# pi-io-board.net
KiCad netlist of a schematic drawn in EAGLE
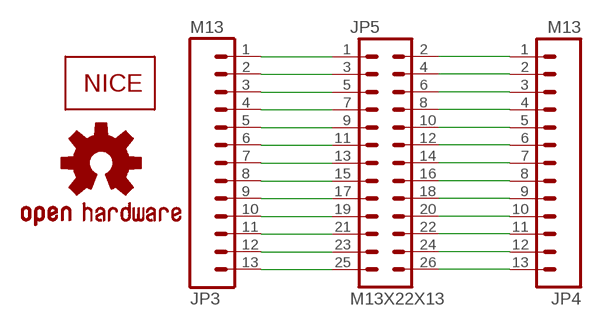
[diagram p0: schematic, sheet 1]

(export (version "E")
  (design (tool "Eeschema 10.0.6"))
  (components
    (comp (ref "JP3")
      (value "M13")
      (footprint "eagle-import:1X13")
      (libsource (lib "eagle-import") (part "M13"))
    )
    (comp (ref "JP4")
      (value "M13")
      (footprint "eagle-import:1X13")
      (libsource (lib "eagle-import") (part "M13"))
    )
    (comp (ref "JP5")
      (value "M13X22X13")
      (footprint "eagle-import:2X13")
      (libsource (lib "eagle-import") (part "M13X22X13"))
    )
    (comp (ref "LOGO1")
      (value "OSHW-LOGOS")
      (footprint "eagle-import:OSHW-LOGO-S")
      (libsource (lib "eagle-import") (part "OSHW-LOGOS"))
    )
    (comp (ref "U$1")
      (value "NICE-LOGO04")
      (footprint "eagle-import:NICE-LOGO-04")
      (libsource (lib "eagle-import") (part "NICE-LOGO04"))
    )
  )
  (nets
    (net (code "1") (name "Net-(JP3-Pad1)") (class "Default")
      (node (ref "JP3") (pin "1") (pinfunction "1_1") (pintype "passive"))
      (node (ref "JP5") (pin "1") (pinfunction "1_1") (pintype "passive"))
    )
    (net (code "2") (name "Net-(JP3-Pad2)") (class "Default")
      (node (ref "JP3") (pin "2") (pinfunction "2_2") (pintype "passive"))
      (node (ref "JP5") (pin "3") (pinfunction "3_3") (pintype "passive"))
    )
    (net (code "3") (name "Net-(JP3-Pad3)") (class "Default")
      (node (ref "JP3") (pin "3") (pinfunction "3_3") (pintype "passive"))
      (node (ref "JP5") (pin "5") (pinfunction "5_5") (pintype "passive"))
    )
    (net (code "4") (name "Net-(JP3-Pad4)") (class "Default")
      (node (ref "JP3") (pin "4") (pinfunction "4_4") (pintype "passive"))
      (node (ref "JP5") (pin "7") (pinfunction "7_7") (pintype "passive"))
    )
    (net (code "5") (name "Net-(JP3-Pad5)") (class "Default")
      (node (ref "JP3") (pin "5") (pinfunction "5_5") (pintype "passive"))
      (node (ref "JP5") (pin "9") (pinfunction "9_9") (pintype "passive"))
    )
    (net (code "6") (name "Net-(JP3-Pad6)") (class "Default")
      (node (ref "JP3") (pin "6") (pinfunction "6_6") (pintype "passive"))
      (node (ref "JP5") (pin "11") (pinfunction "11_11") (pintype "passive"))
    )
    (net (code "7") (name "Net-(JP3-Pad7)") (class "Default")
      (node (ref "JP3") (pin "7") (pinfunction "7_7") (pintype "passive"))
      (node (ref "JP5") (pin "13") (pinfunction "13_13") (pintype "passive"))
    )
    (net (code "8") (name "Net-(JP3-Pad8)") (class "Default")
      (node (ref "JP3") (pin "8") (pinfunction "8_8") (pintype "passive"))
      (node (ref "JP5") (pin "15") (pinfunction "15_15") (pintype "passive"))
    )
    (net (code "9") (name "Net-(JP3-Pad9)") (class "Default")
      (node (ref "JP3") (pin "9") (pinfunction "9_9") (pintype "passive"))
      (node (ref "JP5") (pin "17") (pinfunction "17_17") (pintype "passive"))
    )
    (net (code "10") (name "Net-(JP3-Pad10)") (class "Default")
      (node (ref "JP3") (pin "10") (pinfunction "10_10") (pintype "passive"))
      (node (ref "JP5") (pin "19") (pinfunction "19_19") (pintype "passive"))
    )
    (net (code "11") (name "Net-(JP3-Pad11)") (class "Default")
      (node (ref "JP3") (pin "11") (pinfunction "11_11") (pintype "passive"))
      (node (ref "JP5") (pin "21") (pinfunction "21_21") (pintype "passive"))
    )
    (net (code "12") (name "Net-(JP3-Pad12)") (class "Default")
      (node (ref "JP3") (pin "12") (pinfunction "12_12") (pintype "passive"))
      (node (ref "JP5") (pin "23") (pinfunction "23_23") (pintype "passive"))
    )
    (net (code "13") (name "Net-(JP3-Pad13)") (class "Default")
      (node (ref "JP3") (pin "13") (pinfunction "13_13") (pintype "passive"))
      (node (ref "JP5") (pin "25") (pinfunction "25_25") (pintype "passive"))
    )
    (net (code "14") (name "Net-(JP4-Pad1)") (class "Default")
      (node (ref "JP4") (pin "1") (pinfunction "1_1") (pintype "passive"))
      (node (ref "JP5") (pin "2") (pinfunction "2_2") (pintype "passive"))
    )
    (net (code "15") (name "Net-(JP4-Pad2)") (class "Default")
      (node (ref "JP4") (pin "2") (pinfunction "2_2") (pintype "passive"))
      (node (ref "JP5") (pin "4") (pinfunction "4_4") (pintype "passive"))
    )
    (net (code "16") (name "Net-(JP4-Pad3)") (class "Default")
      (node (ref "JP4") (pin "3") (pinfunction "3_3") (pintype "passive"))
      (node (ref "JP5") (pin "6") (pinfunction "6_6") (pintype "passive"))
    )
    (net (code "17") (name "Net-(JP4-Pad4)") (class "Default")
      (node (ref "JP4") (pin "4") (pinfunction "4_4") (pintype "passive"))
      (node (ref "JP5") (pin "8") (pinfunction "8_8") (pintype "passive"))
    )
    (net (code "18") (name "Net-(JP4-Pad5)") (class "Default")
      (node (ref "JP4") (pin "5") (pinfunction "5_5") (pintype "passive"))
      (node (ref "JP5") (pin "10") (pinfunction "10_10") (pintype "passive"))
    )
    (net (code "19") (name "Net-(JP4-Pad6)") (class "Default")
      (node (ref "JP4") (pin "6") (pinfunction "6_6") (pintype "passive"))
      (node (ref "JP5") (pin "12") (pinfunction "12_12") (pintype "passive"))
    )
    (net (code "20") (name "Net-(JP4-Pad7)") (class "Default")
      (node (ref "JP4") (pin "7") (pinfunction "7_7") (pintype "passive"))
      (node (ref "JP5") (pin "14") (pinfunction "14_14") (pintype "passive"))
    )
    (net (code "21") (name "Net-(JP4-Pad8)") (class "Default")
      (node (ref "JP4") (pin "8") (pinfunction "8_8") (pintype "passive"))
      (node (ref "JP5") (pin "16") (pinfunction "16_16") (pintype "passive"))
    )
    (net (code "22") (name "Net-(JP4-Pad9)") (class "Default")
      (node (ref "JP4") (pin "9") (pinfunction "9_9") (pintype "passive"))
      (node (ref "JP5") (pin "18") (pinfunction "18_18") (pintype "passive"))
    )
    (net (code "23") (name "Net-(JP4-Pad10)") (class "Default")
      (node (ref "JP4") (pin "10") (pinfunction "10_10") (pintype "passive"))
      (node (ref "JP5") (pin "20") (pinfunction "20_20") (pintype "passive"))
    )
    (net (code "24") (name "Net-(JP4-Pad11)") (class "Default")
      (node (ref "JP4") (pin "11") (pinfunction "11_11") (pintype "passive"))
      (node (ref "JP5") (pin "22") (pinfunction "22_22") (pintype "passive"))
    )
    (net (code "25") (name "Net-(JP4-Pad12)") (class "Default")
      (node (ref "JP4") (pin "12") (pinfunction "12_12") (pintype "passive"))
      (node (ref "JP5") (pin "24") (pinfunction "24_24") (pintype "passive"))
    )
    (net (code "26") (name "Net-(JP4-Pad13)") (class "Default")
      (node (ref "JP4") (pin "13") (pinfunction "13_13") (pintype "passive"))
      (node (ref "JP5") (pin "26") (pinfunction "26_26") (pintype "passive"))
    )
  )
)
